# Power_ORing.net
KiCad netlist of a schematic drawn in Altium Designer
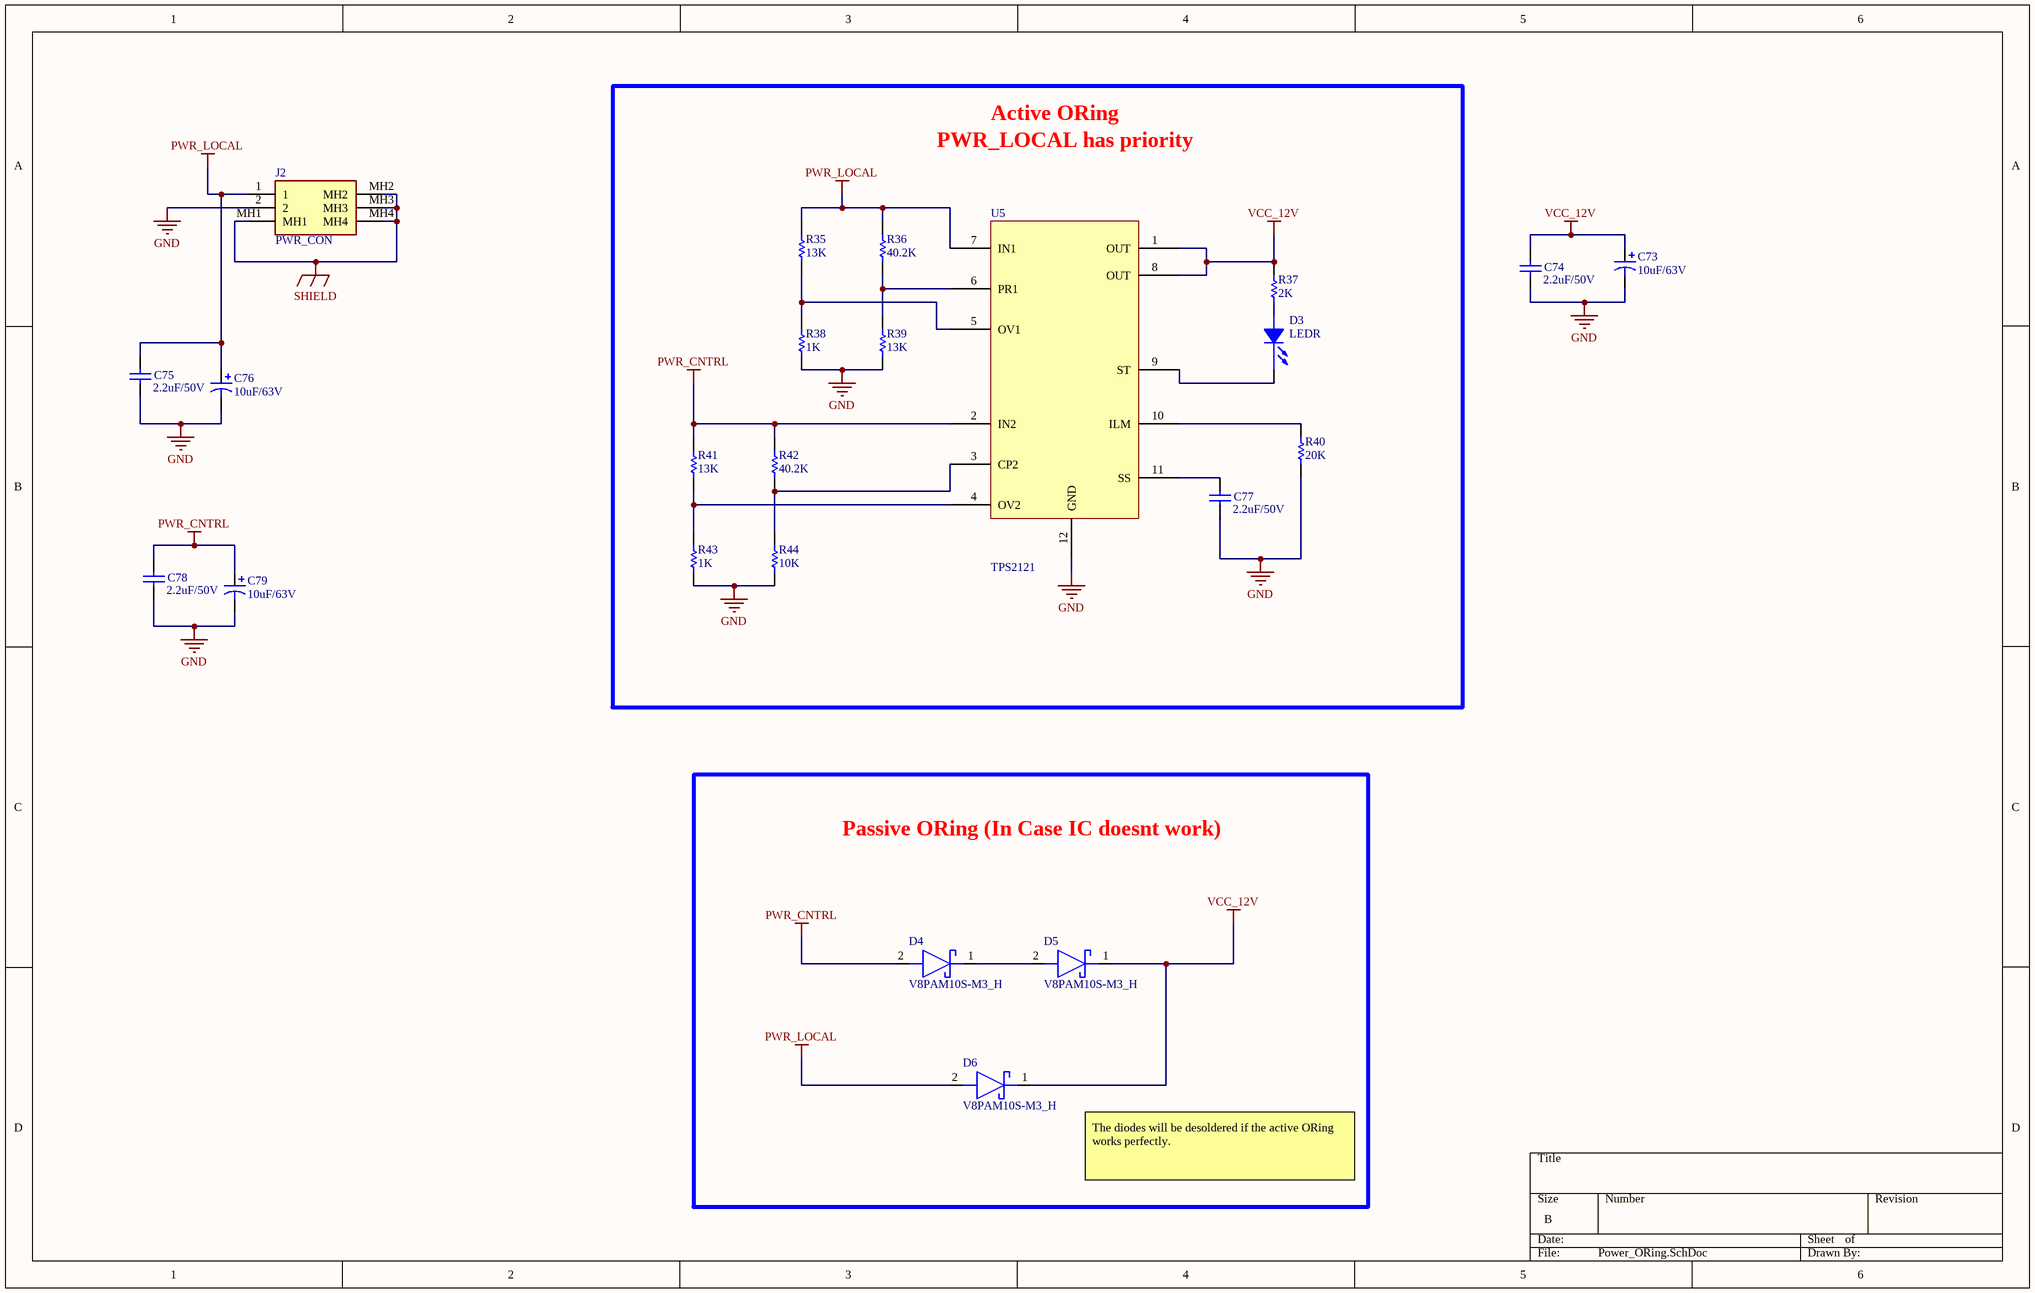
[diagram p0: Power_ORing.SchDoc]

(export (version "E")
  (design (tool "Eeschema 10.0.6"))
  (components
    (comp (ref "C73")
      (value "10uF/63V")
      (footprint "EEE-FN1J100L")
      (description "Polarized Capacitor (Radial)")
      (fields (field (name "MFR") "Panasonic") (field (name "MFR PART NO") "EEE-FN1J100L"))
      (libsource (lib "Miscellaneous Devices") (part "Cap Pol1"))
    )
    (comp (ref "C74")
      (value "2.2uF/50V")
      (footprint "0603C")
      (description "Multilayer Ceramic Capacitors MLCC - SMD/SMT 0603 2.2uF 20% 50VDC X5R")
      (fields (field (name "MFR") "Murata Electronics") (field (name "MFR PART NO") "GRM188R61H225ME11J"))
      (libsource (lib "Miscellaneous Devices") (part "Cap"))
    )
    (comp (ref "C75")
      (value "2.2uF/50V")
      (footprint "0603C")
      (description "Multilayer Ceramic Capacitors MLCC - SMD/SMT 0603 2.2uF 20% 50VDC X5R")
      (fields (field (name "MFR") "Murata Electronics") (field (name "MFR PART NO") "GRM188R61H225ME11J"))
      (libsource (lib "Miscellaneous Devices") (part "Cap"))
    )
    (comp (ref "C76")
      (value "10uF/63V")
      (footprint "EEE-FN1J100L")
      (description "Polarized Capacitor (Radial)")
      (fields (field (name "MFR") "Panasonic") (field (name "MFR PART NO") "EEE-FN1J100L"))
      (libsource (lib "Miscellaneous Devices") (part "Cap Pol1"))
    )
    (comp (ref "C77")
      (value "2.2uF/50V")
      (footprint "0603C")
      (description "Multilayer Ceramic Capacitors MLCC - SMD/SMT 0603 2.2uF 20% 50VDC X5R")
      (fields (field (name "MFR") "Murata Electronics") (field (name "MFR PART NO") "GRM188R61H225ME11J"))
      (libsource (lib "Miscellaneous Devices") (part "Cap"))
    )
    (comp (ref "C78")
      (value "2.2uF/50V")
      (footprint "0603C")
      (description "Multilayer Ceramic Capacitors MLCC - SMD/SMT 0603 2.2uF 20% 50VDC X5R")
      (fields (field (name "MFR") "Murata Electronics") (field (name "MFR PART NO") "GRM188R61H225ME11J"))
      (libsource (lib "Miscellaneous Devices") (part "Cap"))
    )
    (comp (ref "C79")
      (value "10uF/63V")
      (footprint "EEE-FN1J100L")
      (description "Polarized Capacitor (Radial)")
      (fields (field (name "MFR") "Panasonic") (field (name "MFR PART NO") "EEE-FN1J100L"))
      (libsource (lib "Miscellaneous Devices") (part "Cap Pol1"))
    )
    (comp (ref "D3")
      (value "LEDR")
      (footprint "LED_0603")
      (description "Standard LEDs - SMD Red 631nm 14mcd 5mA")
      (fields (field (name "MFR") "Lite-On") (field (name "MFR PART NO") "LTST-C193KRKT-5A"))
      (libsource (lib "de20") (part "LED"))
    )
    (comp (ref "D4")
      (value "V8PAM10S-M3_H")
      (footprint "SamacSys:V8PAM10SHM3H")
      (description "Schottky Diodes & Rectifiers 8A 100V")
      (fields
        (field (name "MFR") "Vishay General Semiconductor")
        (field (name "MFR PART NO") "V8PAM10S-M3/H")
      )
      (libsource (lib "*") (part "V8PAM10S-M3_H"))
    )
    (comp (ref "D5")
      (value "V8PAM10S-M3_H")
      (footprint "SamacSys:V8PAM10SHM3H")
      (description "Schottky Diodes & Rectifiers 8A 100V")
      (fields
        (field (name "MFR") "Vishay General Semiconductor")
        (field (name "MFR PART NO") "V8PAM10S-M3/H")
      )
      (libsource (lib "*") (part "V8PAM10S-M3_H"))
    )
    (comp (ref "D6")
      (value "V8PAM10S-M3_H")
      (footprint "SamacSys:V8PAM10SHM3H")
      (description "Schottky Diodes & Rectifiers 8A 100V")
      (fields
        (field (name "MFR") "Vishay General Semiconductor")
        (field (name "MFR PART NO") "V8PAM10S-M3/H")
      )
      (libsource (lib "*") (part "V8PAM10S-M3_H"))
    )
    (comp (ref "J2")
      (value "PWR_CON")
      (footprint "SamacSys:PJ082BH")
      (description "DC Power Connectors 2.5mm x 5.5mm horz")
      (fields (field (name "MFR") "CUI Devices") (field (name "MFR PART NO") "PJ-082BH"))
      (libsource (lib "*") (part "PJ-082BH"))
    )
    (comp (ref "R35")
      (value "13K")
      (footprint "0603R")
      (description "Thin Film Resistors - SMD 13K ohm 0.1% 25 ppm")
      (fields (field (name "MFR") "KOA Speer") (field (name "MFR PART NO") "RN73R1JTTD1302B25"))
      (libsource (lib "Miscellaneous Devices") (part "Res1"))
    )
    (comp (ref "R36")
      (value "40.2K")
      (footprint "0603R")
      (description "Thick Film Resistors - SMD 0603 Anti-Surge Res. 0.1%, 40.2Koh")
      (fields (field (name "MFR") "Panasonic") (field (name "MFR PART NO") "ERJ-PB3B4022V"))
      (libsource (lib "Miscellaneous Devices") (part "Res1"))
    )
    (comp (ref "R37")
      (value "2K")
      (footprint "0603R")
      (description "Thick Film Resistors - SMD 0603 10Kohms 1% Anti-Sulfur AEC-Q200")
      (fields (field (name "MFR") "ROHM Semiconductor") (field (name "MFR PART NO") "SFR03EZPF1002"))
      (libsource (lib "Miscellaneous Devices") (part "Res1"))
    )
    (comp (ref "R38")
      (value "1K")
      (footprint "0603R")
      (description "Resistor")
      (fields (field (name "MFR") "Vishay / Dale") (field (name "MFR PART NO") "CRCW06031K00FKEAC"))
      (libsource (lib "Miscellaneous Devices") (part "Res1"))
    )
    (comp (ref "R39")
      (value "13K")
      (footprint "0603R")
      (description "Thin Film Resistors - SMD 13K ohm 0.1% 25 ppm")
      (fields (field (name "MFR") "KOA Speer") (field (name "MFR PART NO") "RN73R1JTTD1302B25"))
      (libsource (lib "Miscellaneous Devices") (part "Res1"))
    )
    (comp (ref "R40")
      (value "20K")
      (footprint "0603R")
      (description "Thick Film Resistors - SMD 20K OHM .1% 25PPM")
      (fields (field (name "MFR") "KOA Speer") (field (name "MFR PART NO") "RS73F1JTTD2002B"))
      (libsource (lib "Miscellaneous Devices") (part "Res1"))
    )
    (comp (ref "R41")
      (value "13K")
      (footprint "0603R")
      (description "Thin Film Resistors - SMD 13K ohm 0.1% 25 ppm")
      (fields (field (name "MFR") "KOA Speer") (field (name "MFR PART NO") "RN73R1JTTD1302B25"))
      (libsource (lib "Miscellaneous Devices") (part "Res1"))
    )
    (comp (ref "R42")
      (value "40.2K")
      (footprint "0603R")
      (description "Thick Film Resistors - SMD 0603 Anti-Surge Res. 0.1%, 40.2Koh")
      (fields (field (name "MFR") "Panasonic") (field (name "MFR PART NO") "ERJ-PB3B4022V"))
      (libsource (lib "Miscellaneous Devices") (part "Res1"))
    )
    (comp (ref "R43")
      (value "1K")
      (footprint "0603R")
      (description "Resistor")
      (fields (field (name "MFR") "Vishay / Dale") (field (name "MFR PART NO") "CRCW06031K00FKEAC"))
      (libsource (lib "Miscellaneous Devices") (part "Res1"))
    )
    (comp (ref "R44")
      (value "10K")
      (footprint "0603R")
      (description "Thick Film Resistors - SMD 0603 10Kohms 1% Anti-Sulfur AEC-Q200")
      (fields (field (name "MFR") "ROHM Semiconductor") (field (name "MFR PART NO") "SFR03EZPF1002"))
      (libsource (lib "Miscellaneous Devices") (part "Res1"))
    )
    (comp (ref "U5")
      (value "TPS2121")
      (description "Power Switch ICs - Power Distribution")
      (fields (field (name "MFR") "Texas Instruments") (field (name "MFR PART NO") "TPS2121RUXT"))
      (libsource (lib "Schlib1") (part "TPS2121"))
    )
  )
  (nets
    (net (code "1") (name "GND") (class "Default")
      (node (ref "C73") (pin "2") (pinfunction "2_2") (pintype "passive"))
      (node (ref "C74") (pin "1") (pinfunction "1_1") (pintype "passive"))
      (node (ref "C75") (pin "1") (pinfunction "1_1") (pintype "passive"))
      (node (ref "C76") (pin "2") (pinfunction "2_2") (pintype "passive"))
      (node (ref "C77") (pin "1") (pinfunction "1_1") (pintype "passive"))
      (node (ref "C78") (pin "1") (pinfunction "1_1") (pintype "passive"))
      (node (ref "C79") (pin "2") (pinfunction "2_2") (pintype "passive"))
      (node (ref "J2") (pin "2") (pinfunction "2_2") (pintype "passive"))
      (node (ref "R38") (pin "1") (pinfunction "1_1") (pintype "passive"))
      (node (ref "R39") (pin "2") (pinfunction "2_2") (pintype "passive"))
      (node (ref "R40") (pin "2") (pinfunction "2_2") (pintype "passive"))
      (node (ref "R43") (pin "1") (pinfunction "1_1") (pintype "passive"))
      (node (ref "R44") (pin "2") (pinfunction "2_2") (pintype "passive"))
      (node (ref "U5") (pin "12") (pinfunction "GND_12") (pintype "passive"))
    )
    (net (code "2") (name "Net-(D3-ANODE)") (class "Default")
      (node (ref "D3") (pin "1") (pinfunction "ANODE_1") (pintype "passive"))
      (node (ref "R37") (pin "2") (pinfunction "2_2") (pintype "passive"))
    )
    (net (code "3") (name "Net-(D3-CATHODE)") (class "Default")
      (node (ref "D3") (pin "2") (pinfunction "CATHODE_2") (pintype "passive"))
      (node (ref "U5") (pin "9") (pinfunction "ST_9") (pintype "passive"))
    )
    (net (code "4") (name "Net-(D4-K)") (class "Default")
      (node (ref "D4") (pin "1") (pinfunction "K_1") (pintype "passive"))
      (node (ref "D5") (pin "2") (pinfunction "A_2") (pintype "passive"))
    )
    (net (code "5") (name "Net-(U5-CP2)") (class "Default")
      (node (ref "R42") (pin "1") (pinfunction "1_1") (pintype "passive"))
      (node (ref "R44") (pin "1") (pinfunction "1_1") (pintype "passive"))
      (node (ref "U5") (pin "3") (pinfunction "CP2_3") (pintype "passive"))
    )
    (net (code "6") (name "Net-(U5-ILM)") (class "Default")
      (node (ref "R40") (pin "1") (pinfunction "1_1") (pintype "passive"))
      (node (ref "U5") (pin "10") (pinfunction "ILM_10") (pintype "passive"))
    )
    (net (code "7") (name "Net-(U5-OV1)") (class "Default")
      (node (ref "R35") (pin "2") (pinfunction "2_2") (pintype "passive"))
      (node (ref "R38") (pin "2") (pinfunction "2_2") (pintype "passive"))
      (node (ref "U5") (pin "5") (pinfunction "OV1_5") (pintype "passive"))
    )
    (net (code "8") (name "Net-(U5-OV2)") (class "Default")
      (node (ref "R41") (pin "2") (pinfunction "2_2") (pintype "passive"))
      (node (ref "R43") (pin "2") (pinfunction "2_2") (pintype "passive"))
      (node (ref "U5") (pin "4") (pinfunction "OV2_4") (pintype "passive"))
    )
    (net (code "9") (name "Net-(U5-PR1)") (class "Default")
      (node (ref "R36") (pin "1") (pinfunction "1_1") (pintype "passive"))
      (node (ref "R39") (pin "1") (pinfunction "1_1") (pintype "passive"))
      (node (ref "U5") (pin "6") (pinfunction "PR1_6") (pintype "passive"))
    )
    (net (code "10") (name "Net-(U5-SS)") (class "Default")
      (node (ref "C77") (pin "2") (pinfunction "2_2") (pintype "passive"))
      (node (ref "U5") (pin "11") (pinfunction "SS_11") (pintype "passive"))
    )
    (net (code "11") (name "PWR_CNTRL") (class "Default")
      (node (ref "C78") (pin "2") (pinfunction "2_2") (pintype "passive"))
      (node (ref "C79") (pin "1") (pinfunction "1_1") (pintype "passive"))
      (node (ref "D4") (pin "2") (pinfunction "A_2") (pintype "passive"))
      (node (ref "R41") (pin "1") (pinfunction "1_1") (pintype "passive"))
      (node (ref "R42") (pin "2") (pinfunction "2_2") (pintype "passive"))
      (node (ref "U5") (pin "2") (pinfunction "IN2_2") (pintype "passive"))
    )
    (net (code "12") (name "PWR_LOCAL") (class "Default")
      (node (ref "C75") (pin "2") (pinfunction "2_2") (pintype "passive"))
      (node (ref "C76") (pin "1") (pinfunction "1_1") (pintype "passive"))
      (node (ref "D6") (pin "2") (pinfunction "A_2") (pintype "passive"))
      (node (ref "J2") (pin "1") (pinfunction "1_1") (pintype "passive"))
      (node (ref "R35") (pin "1") (pinfunction "1_1") (pintype "passive"))
      (node (ref "R36") (pin "2") (pinfunction "2_2") (pintype "passive"))
      (node (ref "U5") (pin "7") (pinfunction "IN1_7") (pintype "passive"))
    )
    (net (code "13") (name "SHIELD") (class "Default")
      (node (ref "J2") (pin "MH1") (pinfunction "MH1_MH1") (pintype "passive"))
      (node (ref "J2") (pin "MH2") (pinfunction "MH2_MH2") (pintype "passive"))
      (node (ref "J2") (pin "MH3") (pinfunction "MH3_MH3") (pintype "passive"))
      (node (ref "J2") (pin "MH4") (pinfunction "MH4_MH4") (pintype "passive"))
    )
    (net (code "14") (name "VCC_12V") (class "Default")
      (node (ref "C73") (pin "1") (pinfunction "1_1") (pintype "passive"))
      (node (ref "C74") (pin "2") (pinfunction "2_2") (pintype "passive"))
      (node (ref "D5") (pin "1") (pinfunction "K_1") (pintype "passive"))
      (node (ref "D6") (pin "1") (pinfunction "K_1") (pintype "passive"))
      (node (ref "R37") (pin "1") (pinfunction "1_1") (pintype "passive"))
      (node (ref "U5") (pin "1") (pinfunction "OUT_1") (pintype "passive"))
      (node (ref "U5") (pin "8") (pinfunction "OUT_8") (pintype "passive"))
    )
  )
)
